# sensor_board.net
KiCad netlist of a schematic drawn in EAGLE
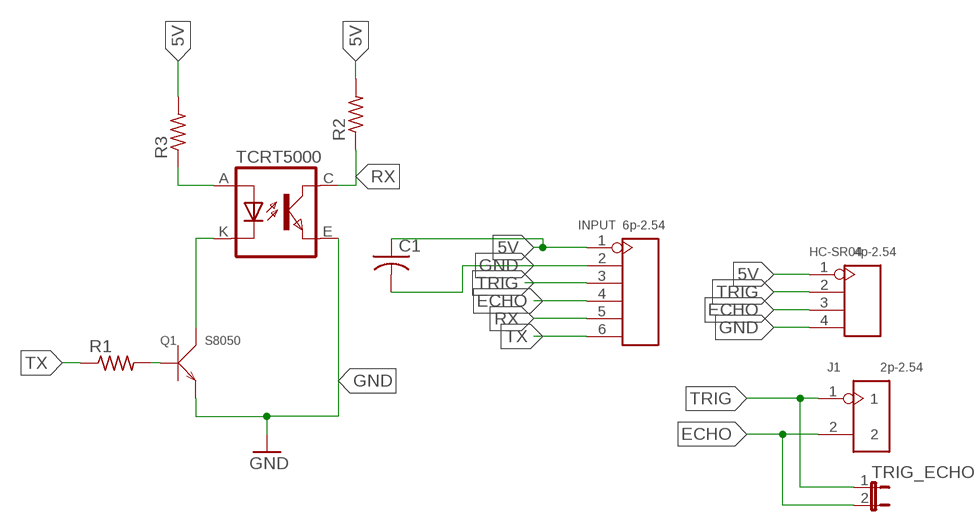
[diagram p0: schematic, sheet 1]

(export (version "E")
  (design (tool "Eeschema 10.0.6"))
  (components
    (comp (ref "C1")
      (value "C-USC1206")
      (footprint "eagle-import:C1206")
      (libsource (lib "eagle-import") (part "C-USC1206"))
    )
    (comp (ref "HC-SR04")
      (value "4p-2.54")
      (footprint "eagle-import:H4-2.54")
      (fields (field (name "MPN") "F185-1104A1BSYA1"))
      (libsource (lib "eagle-import") (part "DIP-BLACK-FEMALE-HEADER-VERT(4P-2.54)"))
    )
    (comp (ref "INPUT")
      (value "6p-2.54")
      (footprint "eagle-import:H6-2.54")
      (fields (field (name "MPN") "F185-1106A1BSYC1"))
      (libsource (lib "eagle-import") (part "DIP-BLACK-FEMALE-HEADER-VERT(6P-2.54)"))
    )
    (comp (ref "J1")
      (value "2p-2.54")
      (footprint "eagle-import:H2-2.54")
      (fields (field (name "MPN") "P125-1102A0BS116A1"))
      (libsource (lib "eagle-import") (part "DIP-BLACK-MALE-HEADER-VERT(2P-2.54)"))
    )
    (comp (ref "Q1")
      (value "S8050")
      (footprint "eagle-import:SOT-23")
      (libsource (lib "eagle-import") (part "SMD-TRANSISTORS-NPN-25V-500MW-S8050(SOT-23)"))
    )
    (comp (ref "R1")
      (value "R-US_R1206")
      (footprint "eagle-import:R1206")
      (libsource (lib "eagle-import") (part "R-US_R1206"))
    )
    (comp (ref "R2")
      (value "R-US_R1206")
      (footprint "eagle-import:R1206")
      (libsource (lib "eagle-import") (part "R-US_R1206"))
    )
    (comp (ref "R3")
      (value "R-US_R1206")
      (footprint "eagle-import:R1206")
      (libsource (lib "eagle-import") (part "R-US_R1206"))
    )
    (comp (ref "TCRT5000")
      (value "TCRT5000")
      (footprint "eagle-import:TCRT5000")
      (libsource (lib "eagle-import") (part "TCRT5000"))
    )
    (comp (ref "TRIG_ECHO")
      (value "JUMPER-2SMD-NC")
      (footprint "eagle-import:SJ_2S")
      (libsource (lib "eagle-import") (part "JUMPER-2SMD-NC"))
    )
  )
  (nets
    (net (code "1") (name "5V") (class "Default")
      (node (ref "C1") (pin "1") (pinfunction "1_1") (pintype "passive"))
      (node (ref "HC-SR04") (pin "1") (pinfunction "P$1_1") (pintype "bidirectional"))
      (node (ref "INPUT") (pin "1") (pinfunction "1_1") (pintype "bidirectional"))
      (node (ref "R2") (pin "2") (pinfunction "2_2") (pintype "passive"))
      (node (ref "R3") (pin "2") (pinfunction "2_2") (pintype "passive"))
    )
    (net (code "2") (name "ECHO") (class "Default")
      (node (ref "HC-SR04") (pin "3") (pinfunction "P$3_3") (pintype "bidirectional"))
      (node (ref "INPUT") (pin "4") (pinfunction "4_4") (pintype "bidirectional"))
      (node (ref "J1") (pin "2") (pinfunction "2_2") (pintype "bidirectional"))
      (node (ref "TRIG_ECHO") (pin "2") (pinfunction "2_2") (pintype "passive"))
    )
    (net (code "3") (name "GND") (class "Default")
      (node (ref "C1") (pin "2") (pinfunction "2_2") (pintype "passive"))
      (node (ref "HC-SR04") (pin "4") (pinfunction "P$4_4") (pintype "bidirectional"))
      (node (ref "INPUT") (pin "2") (pinfunction "2_2") (pintype "bidirectional"))
      (node (ref "Q1") (pin "2") (pinfunction "E_2") (pintype "passive"))
      (node (ref "TCRT5000") (pin "E") (pinfunction "EMITTER_E") (pintype "passive"))
    )
    (net (code "4") (name "Net-(Q1-B)") (class "Default")
      (node (ref "Q1") (pin "1") (pinfunction "B_1") (pintype "passive"))
      (node (ref "R1") (pin "2") (pinfunction "2_2") (pintype "passive"))
    )
    (net (code "5") (name "Net-(Q1-C)") (class "Default")
      (node (ref "Q1") (pin "3") (pinfunction "C_3") (pintype "passive"))
      (node (ref "TCRT5000") (pin "K") (pinfunction "CATHODE_K") (pintype "passive"))
    )
    (net (code "6") (name "Net-(TCRT5000-ANODE)") (class "Default")
      (node (ref "R3") (pin "1") (pinfunction "1_1") (pintype "passive"))
      (node (ref "TCRT5000") (pin "A") (pinfunction "ANODE_A") (pintype "passive"))
    )
    (net (code "7") (name "RX") (class "Default")
      (node (ref "INPUT") (pin "5") (pinfunction "5_5") (pintype "bidirectional"))
      (node (ref "R2") (pin "1") (pinfunction "1_1") (pintype "passive"))
      (node (ref "TCRT5000") (pin "C") (pinfunction "COLLECTOR_C") (pintype "passive"))
    )
    (net (code "8") (name "TRIG") (class "Default")
      (node (ref "HC-SR04") (pin "2") (pinfunction "P$2_2") (pintype "bidirectional"))
      (node (ref "INPUT") (pin "3") (pinfunction "3_3") (pintype "bidirectional"))
      (node (ref "J1") (pin "1") (pinfunction "1_1") (pintype "bidirectional"))
      (node (ref "TRIG_ECHO") (pin "1") (pinfunction "1_1") (pintype "passive"))
    )
    (net (code "9") (name "TX") (class "Default")
      (node (ref "INPUT") (pin "6") (pinfunction "6_6") (pintype "bidirectional"))
      (node (ref "R1") (pin "1") (pinfunction "1_1") (pintype "passive"))
    )
  )
)
